# rosscomp_th.net
KiCad netlist of a schematic drawn in EAGLE
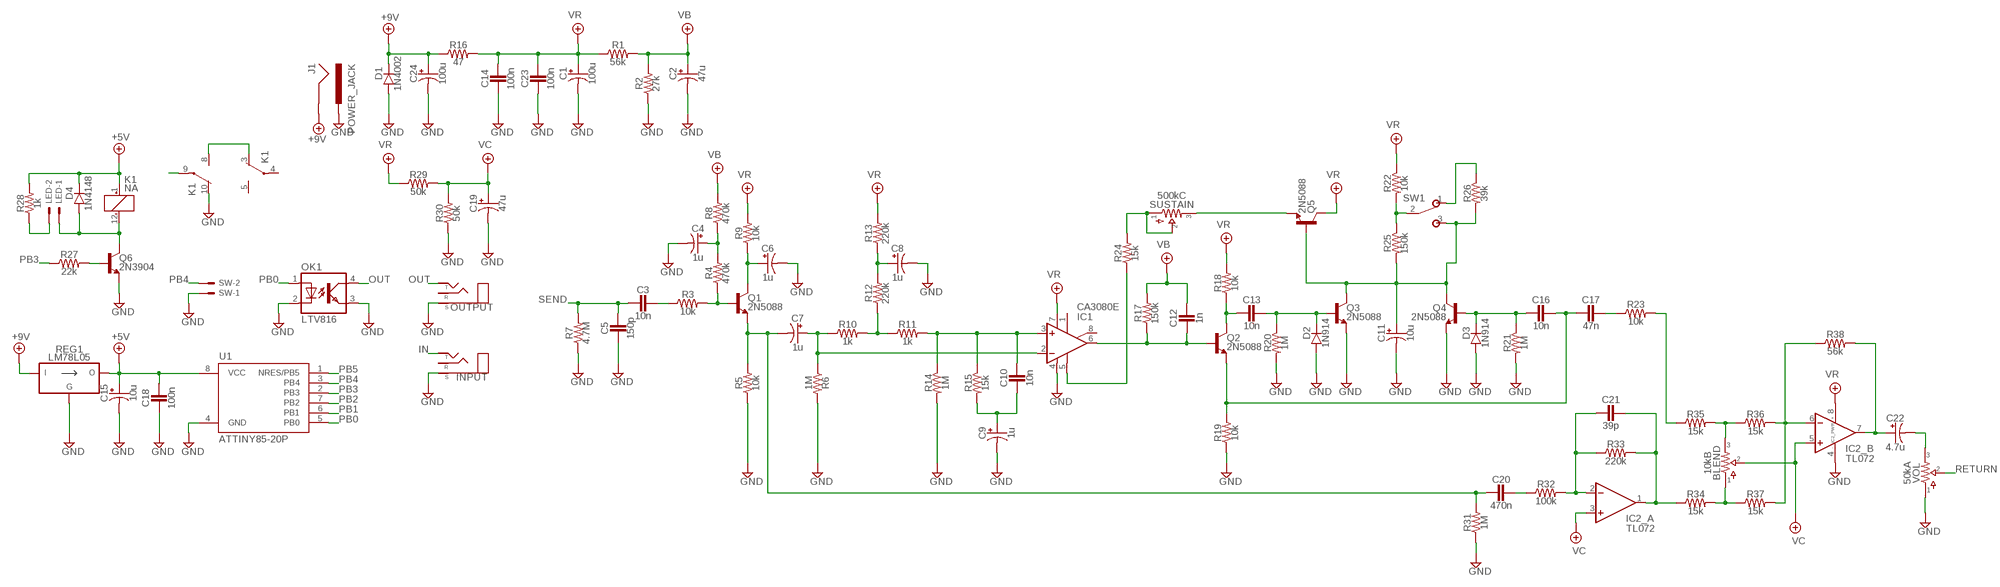
[diagram p0: schematic, sheet 1]

(export (version "E")
  (design (tool "Eeschema 10.0.6"))
  (components
    (comp (ref "BLEND")
      (value "10kB")
      (footprint "eagle-import:16MM")
      (libsource (lib "eagle-import") (part "POTS16MM"))
    )
    (comp (ref "C1")
      (value "100u")
      (footprint "eagle-import:050_020")
      (libsource (lib "eagle-import") (part "0500"))
    )
    (comp (ref "C2")
      (value "47u")
      (footprint "eagle-import:050_020")
      (libsource (lib "eagle-import") (part "0500"))
    )
    (comp (ref "C3")
      (value "10n")
      (footprint "eagle-import:BOX_SMALL")
      (libsource (lib "eagle-import") (part "CER/FILMBOX.1"))
    )
    (comp (ref "C4")
      (value "1u")
      (footprint "eagle-import:040_020")
      (libsource (lib "eagle-import") (part "0400"))
    )
    (comp (ref "C5")
      (value "150p")
      (footprint "eagle-import:050X030_025_2")
      (libsource (lib "eagle-import") (part "CER/FILM2"))
    )
    (comp (ref "C6")
      (value "1u")
      (footprint "eagle-import:040_020")
      (libsource (lib "eagle-import") (part "0400"))
    )
    (comp (ref "C7")
      (value "1u")
      (footprint "eagle-import:040_020")
      (libsource (lib "eagle-import") (part "0400"))
    )
    (comp (ref "C8")
      (value "1u")
      (footprint "eagle-import:040_020")
      (libsource (lib "eagle-import") (part "0400"))
    )
    (comp (ref "C9")
      (value "1u")
      (footprint "eagle-import:040_020")
      (libsource (lib "eagle-import") (part "0400"))
    )
    (comp (ref "C10")
      (value "10n")
      (footprint "eagle-import:BOX_SMALL")
      (libsource (lib "eagle-import") (part "CER/FILMBOX.1"))
    )
    (comp (ref "C11")
      (value "10u")
      (footprint "eagle-import:050_020")
      (libsource (lib "eagle-import") (part "0500"))
    )
    (comp (ref "C12")
      (value "1n")
      (footprint "eagle-import:BOX_SMALL")
      (libsource (lib "eagle-import") (part "CER/FILMBOX.1"))
    )
    (comp (ref "C13")
      (value "10n")
      (footprint "eagle-import:BOX_SMALL")
      (libsource (lib "eagle-import") (part "CER/FILMBOX.1"))
    )
    (comp (ref "C14")
      (value "100n")
      (footprint "eagle-import:050X030_025_2")
      (libsource (lib "eagle-import") (part "CER/FILM2"))
    )
    (comp (ref "C15")
      (value "10u")
      (footprint "eagle-import:050_020")
      (libsource (lib "eagle-import") (part "0500"))
    )
    (comp (ref "C16")
      (value "10n")
      (footprint "eagle-import:BOX_SMALL")
      (libsource (lib "eagle-import") (part "CER/FILMBOX.1"))
    )
    (comp (ref "C17")
      (value "47n")
      (footprint "eagle-import:BOX_SMALL")
      (libsource (lib "eagle-import") (part "CER/FILMBOX.1"))
    )
    (comp (ref "C18")
      (value "100n")
      (footprint "eagle-import:050X030_025_2")
      (libsource (lib "eagle-import") (part "CER/FILM2"))
    )
    (comp (ref "C19")
      (value "47u")
      (footprint "eagle-import:050_020")
      (libsource (lib "eagle-import") (part "0500"))
    )
    (comp (ref "C20")
      (value "470n")
      (footprint "eagle-import:BOX_MED")
      (libsource (lib "eagle-import") (part "CER/FILMBOX.2"))
    )
    (comp (ref "C21")
      (value "39p")
      (footprint "eagle-import:050X030_025_2")
      (libsource (lib "eagle-import") (part "CER/FILM2"))
    )
    (comp (ref "C22")
      (value "4.7u")
      (footprint "eagle-import:050_020")
      (libsource (lib "eagle-import") (part "0500"))
    )
    (comp (ref "C23")
      (value "100n")
      (footprint "eagle-import:050X030_025_2")
      (libsource (lib "eagle-import") (part "CER/FILM2"))
    )
    (comp (ref "C24")
      (value "100u")
      (footprint "eagle-import:050_020")
      (libsource (lib "eagle-import") (part "0500"))
    )
    (comp (ref "D1")
      (value "1N4002")
      (footprint "eagle-import:DO41-2")
      (libsource (lib "eagle-import") (part "DO41.2"))
    )
    (comp (ref "D2")
      (value "1N914")
      (footprint "eagle-import:DO35-2")
      (libsource (lib "eagle-import") (part "DO35.2"))
    )
    (comp (ref "D3")
      (value "1N914")
      (footprint "eagle-import:DO35-2")
      (libsource (lib "eagle-import") (part "DO35.2"))
    )
    (comp (ref "D4")
      (value "1N4148")
      (footprint "eagle-import:DO35-2")
      (libsource (lib "eagle-import") (part "DO35.2"))
    )
    (comp (ref "IC1")
      (value "CA3080E")
      (footprint "eagle-import:DIL0")
      (libsource (lib "eagle-import") (part "3080TH"))
    )
    (comp (ref "IC2")
      (value "TL072")
      (footprint "eagle-import:DIL0")
      (libsource (lib "eagle-import") (part "DUALTH"))
    )
    (comp (ref "INPUT")
      (value "STEREONMJ")
      (footprint "eagle-import:NMJ6HCD2")
      (libsource (lib "eagle-import") (part "STEREONMJ"))
    )
    (comp (ref "J1")
      (value "POWER_JACK")
      (footprint "eagle-import:POWER_JACK_PTH")
      (libsource (lib "eagle-import") (part "POWER_JACK"))
    )
    (comp (ref "K1") (value "NA") (footprint "eagle-import:NA") (libsource (lib "eagle-import") (part "NA")))
    (comp (ref "LED")
      (value "JST-XH-02-PIN-ROUND-PAD")
      (footprint "eagle-import:JST-XH-02-PACKAGE-ROUND-PAD")
      (libsource (lib "eagle-import") (part "JST-XH-02-PIN-ROUND-PAD"))
    )
    (comp (ref "OK1")
      (value "LTV816")
      (footprint "eagle-import:DIL04")
      (libsource (lib "eagle-import") (part "LTV816"))
    )
    (comp (ref "OUTPUT")
      (value "STEREONMJ")
      (footprint "eagle-import:NMJ6HCD2")
      (libsource (lib "eagle-import") (part "STEREONMJ"))
    )
    (comp (ref "Q1")
      (value "2N5088")
      (footprint "eagle-import:TO92-")
      (libsource (lib "eagle-import") (part "2N5088"))
    )
    (comp (ref "Q2")
      (value "2N5088")
      (footprint "eagle-import:TO92-")
      (libsource (lib "eagle-import") (part "2N5088"))
    )
    (comp (ref "Q3")
      (value "2N5088")
      (footprint "eagle-import:TO92-")
      (libsource (lib "eagle-import") (part "2N5088"))
    )
    (comp (ref "Q4")
      (value "2N5088")
      (footprint "eagle-import:TO92-")
      (libsource (lib "eagle-import") (part "2N5088"))
    )
    (comp (ref "Q5")
      (value "2N5088")
      (footprint "eagle-import:TO92-")
      (libsource (lib "eagle-import") (part "2N5088"))
    )
    (comp (ref "Q6")
      (value "2N3904")
      (footprint "eagle-import:TO92-")
      (libsource (lib "eagle-import") (part "2N3904"))
    )
    (comp (ref "R1")
      (value "56k")
      (footprint "eagle-import:R0207_3")
      (libsource (lib "eagle-import") (part "R_.3B"))
    )
    (comp (ref "R2")
      (value "27k")
      (footprint "eagle-import:R0207_3")
      (libsource (lib "eagle-import") (part "R_.3B"))
    )
    (comp (ref "R3")
      (value "10k")
      (footprint "eagle-import:R0207_3")
      (libsource (lib "eagle-import") (part "R_.3B"))
    )
    (comp (ref "R4")
      (value "470k")
      (footprint "eagle-import:R0207_3")
      (libsource (lib "eagle-import") (part "R_.3B"))
    )
    (comp (ref "R5")
      (value "10k")
      (footprint "eagle-import:R0207_3")
      (libsource (lib "eagle-import") (part "R_.3B"))
    )
    (comp (ref "R6")
      (value "1M")
      (footprint "eagle-import:R0207_3")
      (libsource (lib "eagle-import") (part "R_.3B"))
    )
    (comp (ref "R7")
      (value "4.7M")
      (footprint "eagle-import:R0207_3")
      (libsource (lib "eagle-import") (part "R_.3B"))
    )
    (comp (ref "R8")
      (value "470k")
      (footprint "eagle-import:R0207_3")
      (libsource (lib "eagle-import") (part "R_.3B"))
    )
    (comp (ref "R9")
      (value "10k")
      (footprint "eagle-import:R0207_3")
      (libsource (lib "eagle-import") (part "R_.3B"))
    )
    (comp (ref "R10")
      (value "1k")
      (footprint "eagle-import:R0207_3")
      (libsource (lib "eagle-import") (part "R_.3B"))
    )
    (comp (ref "R11")
      (value "1k")
      (footprint "eagle-import:R0207_3")
      (libsource (lib "eagle-import") (part "R_.3B"))
    )
    (comp (ref "R12")
      (value "220k")
      (footprint "eagle-import:R0207_3")
      (libsource (lib "eagle-import") (part "R_.3B"))
    )
    (comp (ref "R13")
      (value "220k")
      (footprint "eagle-import:R0207_3")
      (libsource (lib "eagle-import") (part "R_.3B"))
    )
    (comp (ref "R14")
      (value "1M")
      (footprint "eagle-import:R0207_3")
      (libsource (lib "eagle-import") (part "R_.3B"))
    )
    (comp (ref "R15")
      (value "15k")
      (footprint "eagle-import:R0207_3")
      (libsource (lib "eagle-import") (part "R_.3B"))
    )
    (comp (ref "R16")
      (value "47")
      (footprint "eagle-import:R0207_3")
      (libsource (lib "eagle-import") (part "R_.3B"))
    )
    (comp (ref "R17")
      (value "150k")
      (footprint "eagle-import:R0207_3")
      (libsource (lib "eagle-import") (part "R_.3B"))
    )
    (comp (ref "R18")
      (value "10k")
      (footprint "eagle-import:R0207_3")
      (libsource (lib "eagle-import") (part "R_.3B"))
    )
    (comp (ref "R19")
      (value "10k")
      (footprint "eagle-import:R0207_3")
      (libsource (lib "eagle-import") (part "R_.3B"))
    )
    (comp (ref "R20")
      (value "1M")
      (footprint "eagle-import:R0207_3")
      (libsource (lib "eagle-import") (part "R_.3B"))
    )
    (comp (ref "R21")
      (value "1M")
      (footprint "eagle-import:R0207_3")
      (libsource (lib "eagle-import") (part "R_.3B"))
    )
    (comp (ref "R22")
      (value "10k")
      (footprint "eagle-import:R0207_3")
      (libsource (lib "eagle-import") (part "R_.3B"))
    )
    (comp (ref "R23")
      (value "10k")
      (footprint "eagle-import:R0207_3")
      (libsource (lib "eagle-import") (part "R_.3B"))
    )
    (comp (ref "R24")
      (value "15k")
      (footprint "eagle-import:R0207_3")
      (libsource (lib "eagle-import") (part "R_.3B"))
    )
    (comp (ref "R25")
      (value "150k")
      (footprint "eagle-import:R0207_3")
      (libsource (lib "eagle-import") (part "R_.3B"))
    )
    (comp (ref "R26")
      (value "39k")
      (footprint "eagle-import:R0207_3")
      (libsource (lib "eagle-import") (part "R_.3B"))
    )
    (comp (ref "R27")
      (value "22k")
      (footprint "eagle-import:R0207_3")
      (libsource (lib "eagle-import") (part "R_.3B"))
    )
    (comp (ref "R28")
      (value "1k")
      (footprint "eagle-import:R0207_3")
      (libsource (lib "eagle-import") (part "R_.3B"))
    )
    (comp (ref "R29")
      (value "50k")
      (footprint "eagle-import:R0207_3")
      (libsource (lib "eagle-import") (part "R_.3B"))
    )
    (comp (ref "R30")
      (value "50k")
      (footprint "eagle-import:R0207_3")
      (libsource (lib "eagle-import") (part "R_.3B"))
    )
    (comp (ref "R31")
      (value "1M")
      (footprint "eagle-import:R0207_3")
      (libsource (lib "eagle-import") (part "R_.3B"))
    )
    (comp (ref "R32")
      (value "100k")
      (footprint "eagle-import:R0207_3")
      (libsource (lib "eagle-import") (part "R_.3B"))
    )
    (comp (ref "R33")
      (value "220k")
      (footprint "eagle-import:R0207_3")
      (libsource (lib "eagle-import") (part "R_.3B"))
    )
    (comp (ref "R34")
      (value "15k")
      (footprint "eagle-import:R0207_3")
      (libsource (lib "eagle-import") (part "R_.3B"))
    )
    (comp (ref "R35")
      (value "15k")
      (footprint "eagle-import:R0207_3")
      (libsource (lib "eagle-import") (part "R_.3B"))
    )
    (comp (ref "R36")
      (value "15k")
      (footprint "eagle-import:R0207_3")
      (libsource (lib "eagle-import") (part "R_.3B"))
    )
    (comp (ref "R37")
      (value "15k")
      (footprint "eagle-import:R0207_3")
      (libsource (lib "eagle-import") (part "R_.3B"))
    )
    (comp (ref "R38")
      (value "56k")
      (footprint "eagle-import:R0207_3")
      (libsource (lib "eagle-import") (part "R_.3B"))
    )
    (comp (ref "REG1")
      (value "LM78L05")
      (footprint "eagle-import:TO92-")
      (libsource (lib "eagle-import") (part "LM78L05"))
    )
    (comp (ref "SUSTAIN")
      (value "500kC")
      (footprint "eagle-import:16MM")
      (libsource (lib "eagle-import") (part "POTS16MM"))
    )
    (comp (ref "SW")
      (value "JST-XH-02-PIN-ROUND-PAD")
      (footprint "eagle-import:JST-XH-02-PACKAGE-ROUND-PAD")
      (libsource (lib "eagle-import") (part "JST-XH-02-PIN-ROUND-PAD"))
    )
    (comp (ref "SW1")
      (value "SPDT")
      (footprint "eagle-import:M9040P")
      (libsource (lib "eagle-import") (part "SPDT"))
    )
    (comp (ref "U1")
      (value "ATTINY85-20P")
      (footprint "eagle-import:PDIP08_300MIL")
      (libsource (lib "eagle-import") (part "ATTINY85P-20"))
    )
    (comp (ref "VOL")
      (value "50kA")
      (footprint "eagle-import:16MM")
      (libsource (lib "eagle-import") (part "POTS16MM"))
    )
  )
  (nets
    (net (code "1") (name "+5V") (class "Default")
      (node (ref "C15") (pin "+") (pinfunction "+_+") (pintype "passive"))
      (node (ref "C18") (pin "1") (pinfunction "1_1") (pintype "passive"))
      (node (ref "D4") (pin "C") (pinfunction "C_C") (pintype "passive"))
      (node (ref "K1") (pin "1") (pinfunction "+_1") (pintype "passive"))
      (node (ref "R28") (pin "2") (pinfunction "2_2") (pintype "passive"))
      (node (ref "REG1") (pin "3") (pinfunction "VO_3") (pintype "passive"))
      (node (ref "U1") (pin "8") (pinfunction "VCC_8") (pintype "power_in"))
    )
    (net (code "2") (name "+9V") (class "Default")
      (node (ref "C24") (pin "+") (pinfunction "+_+") (pintype "passive"))
      (node (ref "D1") (pin "C") (pinfunction "C_C") (pintype "passive"))
      (node (ref "J1") (pin "GND") (pinfunction "GND_GND") (pintype "bidirectional"))
      (node (ref "R16") (pin "1") (pinfunction "1_1") (pintype "passive"))
      (node (ref "REG1") (pin "1") (pinfunction "VI_1") (pintype "input"))
    )
    (net (code "3") (name "/IN") (class "Default")
      (node (ref "INPUT") (pin "T") (pinfunction "T_T") (pintype "passive"))
    )
    (net (code "4") (name "/OUT") (class "Default")
      (node (ref "OK1") (pin "4") (pinfunction "COL_4") (pintype "passive"))
      (node (ref "OUTPUT") (pin "T") (pinfunction "T_T") (pintype "passive"))
    )
    (net (code "5") (name "/PB0") (class "Default")
      (node (ref "OK1") (pin "1") (pinfunction "A_1") (pintype "passive"))
      (node (ref "U1") (pin "5") (pinfunction "PB0_5") (pintype "bidirectional"))
    )
    (net (code "6") (name "/PB1") (class "Default")
      (node (ref "U1") (pin "6") (pinfunction "PB1_6") (pintype "bidirectional"))
    )
    (net (code "7") (name "/PB2") (class "Default")
      (node (ref "U1") (pin "7") (pinfunction "PB2_7") (pintype "bidirectional"))
    )
    (net (code "8") (name "/PB3") (class "Default")
      (node (ref "R27") (pin "1") (pinfunction "1_1") (pintype "passive"))
      (node (ref "U1") (pin "2") (pinfunction "PB3_2") (pintype "bidirectional"))
    )
    (net (code "9") (name "/PB4") (class "Default")
      (node (ref "SW") (pin "2") (pinfunction "S_2") (pintype "passive"))
      (node (ref "U1") (pin "3") (pinfunction "PB4_3") (pintype "bidirectional"))
    )
    (net (code "10") (name "/PB5") (class "Default")
      (node (ref "U1") (pin "1") (pinfunction "NRES/PB5_1") (pintype "bidirectional"))
    )
    (net (code "11") (name "/RETURN") (class "Default")
      (node (ref "VOL") (pin "2") (pinfunction "2_2") (pintype "passive"))
    )
    (net (code "12") (name "/SEND") (class "Default")
      (node (ref "C3") (pin "2") (pinfunction "2_2") (pintype "passive"))
      (node (ref "C5") (pin "1") (pinfunction "1_1") (pintype "passive"))
      (node (ref "R7") (pin "2") (pinfunction "2_2") (pintype "passive"))
    )
    (net (code "13") (name "GND") (class "Default")
      (node (ref "C1") (pin "-") (pinfunction "-_-") (pintype "passive"))
      (node (ref "C11") (pin "-") (pinfunction "-_-") (pintype "passive"))
      (node (ref "C14") (pin "1") (pinfunction "1_1") (pintype "passive"))
      (node (ref "C15") (pin "-") (pinfunction "-_-") (pintype "passive"))
      (node (ref "C18") (pin "2") (pinfunction "2_2") (pintype "passive"))
      (node (ref "C19") (pin "-") (pinfunction "-_-") (pintype "passive"))
      (node (ref "C2") (pin "-") (pinfunction "-_-") (pintype "passive"))
      (node (ref "C23") (pin "1") (pinfunction "1_1") (pintype "passive"))
      (node (ref "C24") (pin "-") (pinfunction "-_-") (pintype "passive"))
      (node (ref "C4") (pin "-") (pinfunction "-_-") (pintype "passive"))
      (node (ref "C5") (pin "2") (pinfunction "2_2") (pintype "passive"))
      (node (ref "C6") (pin "-") (pinfunction "-_-") (pintype "passive"))
      (node (ref "C8") (pin "-") (pinfunction "-_-") (pintype "passive"))
      (node (ref "C9") (pin "-") (pinfunction "-_-") (pintype "passive"))
      (node (ref "D1") (pin "A") (pinfunction "A_A") (pintype "passive"))
      (node (ref "D2") (pin "A") (pinfunction "A_A") (pintype "passive"))
      (node (ref "D3") (pin "A") (pinfunction "A_A") (pintype "passive"))
      (node (ref "IC1") (pin "4") (pinfunction "V-_4") (pintype "power_in"))
      (node (ref "IC2") (pin "4") (pinfunction "V-_4") (pintype "power_in"))
      (node (ref "INPUT") (pin "S") (pinfunction "S_S") (pintype "passive"))
      (node (ref "J1") (pin "PWR") (pinfunction "PWR_PWR") (pintype "bidirectional"))
      (node (ref "K1") (pin "10") (pinfunction "O_10") (pintype "passive"))
      (node (ref "OK1") (pin "2") (pinfunction "C_2") (pintype "passive"))
      (node (ref "OK1") (pin "3") (pinfunction "EMIT_3") (pintype "passive"))
      (node (ref "OUTPUT") (pin "S") (pinfunction "S_S") (pintype "passive"))
      (node (ref "Q3") (pin "3") (pinfunction "E_3") (pintype "passive"))
      (node (ref "Q4") (pin "3") (pinfunction "E_3") (pintype "passive"))
      (node (ref "Q6") (pin "3") (pinfunction "E_3") (pintype "passive"))
      (node (ref "R14") (pin "2") (pinfunction "2_2") (pintype "passive"))
      (node (ref "R19") (pin "1") (pinfunction "1_1") (pintype "passive"))
      (node (ref "R2") (pin "1") (pinfunction "1_1") (pintype "passive"))
      (node (ref "R20") (pin "2") (pinfunction "2_2") (pintype "passive"))
      (node (ref "R21") (pin "2") (pinfunction "2_2") (pintype "passive"))
      (node (ref "R30") (pin "1") (pinfunction "1_1") (pintype "passive"))
      (node (ref "R31") (pin "1") (pinfunction "1_1") (pintype "passive"))
      (node (ref "R5") (pin "1") (pinfunction "1_1") (pintype "passive"))
      (node (ref "R6") (pin "2") (pinfunction "2_2") (pintype "passive"))
      (node (ref "R7") (pin "1") (pinfunction "1_1") (pintype "passive"))
      (node (ref "REG1") (pin "2") (pinfunction "GND_2") (pintype "passive"))
      (node (ref "SW") (pin "1") (pinfunction "S_1") (pintype "passive"))
      (node (ref "U1") (pin "4") (pinfunction "GND_4") (pintype "power_in"))
      (node (ref "VOL") (pin "1") (pinfunction "1_1") (pintype "passive"))
    )
    (net (code "14") (name "Net-(BLEND-Pad1)") (class "Default")
      (node (ref "BLEND") (pin "1") (pinfunction "1_1") (pintype "passive"))
      (node (ref "R34") (pin "2") (pinfunction "2_2") (pintype "passive"))
      (node (ref "R37") (pin "1") (pinfunction "1_1") (pintype "passive"))
    )
    (net (code "15") (name "Net-(BLEND-Pad3)") (class "Default")
      (node (ref "BLEND") (pin "3") (pinfunction "3_3") (pintype "passive"))
      (node (ref "R35") (pin "2") (pinfunction "2_2") (pintype "passive"))
      (node (ref "R36") (pin "1") (pinfunction "1_1") (pintype "passive"))
    )
    (net (code "16") (name "Net-(C3-Pad1)") (class "Default")
      (node (ref "C3") (pin "1") (pinfunction "1_1") (pintype "passive"))
      (node (ref "R3") (pin "1") (pinfunction "1_1") (pintype "passive"))
    )
    (net (code "17") (name "Net-(C4-Pad+)") (class "Default")
      (node (ref "C4") (pin "+") (pinfunction "+_+") (pintype "passive"))
      (node (ref "R4") (pin "2") (pinfunction "2_2") (pintype "passive"))
      (node (ref "R8") (pin "1") (pinfunction "1_1") (pintype "passive"))
    )
    (net (code "18") (name "Net-(C8-Pad+)") (class "Default")
      (node (ref "C8") (pin "+") (pinfunction "+_+") (pintype "passive"))
      (node (ref "R12") (pin "2") (pinfunction "2_2") (pintype "passive"))
      (node (ref "R13") (pin "1") (pinfunction "1_1") (pintype "passive"))
    )
    (net (code "19") (name "Net-(C10-Pad2)") (class "Default")
      (node (ref "C10") (pin "2") (pinfunction "2_2") (pintype "passive"))
      (node (ref "C9") (pin "+") (pinfunction "+_+") (pintype "passive"))
      (node (ref "R15") (pin "2") (pinfunction "2_2") (pintype "passive"))
    )
    (net (code "20") (name "Net-(C17-Pad1)") (class "Default")
      (node (ref "C17") (pin "1") (pinfunction "1_1") (pintype "passive"))
      (node (ref "R23") (pin "1") (pinfunction "1_1") (pintype "passive"))
    )
    (net (code "21") (name "Net-(C20-Pad1)") (class "Default")
      (node (ref "C20") (pin "1") (pinfunction "1_1") (pintype "passive"))
      (node (ref "R32") (pin "1") (pinfunction "1_1") (pintype "passive"))
    )
    (net (code "22") (name "Net-(C22-Pad-)") (class "Default")
      (node (ref "C22") (pin "-") (pinfunction "-_-") (pintype "passive"))
      (node (ref "VOL") (pin "3") (pinfunction "3_3") (pintype "passive"))
    )
    (net (code "23") (name "Net-(IC1-+IN)") (class "Default")
      (node (ref "C10") (pin "1") (pinfunction "1_1") (pintype "passive"))
      (node (ref "IC1") (pin "3") (pinfunction "+IN_3") (pintype "input"))
      (node (ref "R11") (pin "2") (pinfunction "2_2") (pintype "passive"))
      (node (ref "R14") (pin "1") (pinfunction "1_1") (pintype "passive"))
      (node (ref "R15") (pin "1") (pinfunction "1_1") (pintype "passive"))
    )
    (net (code "24") (name "Net-(IC1--IN)") (class "Default")
      (node (ref "C7") (pin "+") (pinfunction "+_+") (pintype "passive"))
      (node (ref "IC1") (pin "2") (pinfunction "-IN_2") (pintype "input"))
      (node (ref "R10") (pin "1") (pinfunction "1_1") (pintype "passive"))
      (node (ref "R6") (pin "1") (pinfunction "1_1") (pintype "passive"))
    )
    (net (code "25") (name "Net-(IC1-OPT)") (class "Default")
      (node (ref "IC1") (pin "5") (pinfunction "OPT_5") (pintype "passive"))
      (node (ref "R24") (pin "1") (pinfunction "1_1") (pintype "passive"))
    )
    (net (code "26") (name "Net-(IC1-OUT)") (class "Default")
      (node (ref "C12") (pin "2") (pinfunction "2_2") (pintype "passive"))
      (node (ref "IC1") (pin "6") (pinfunction "OUT_6") (pintype "output"))
      (node (ref "Q2") (pin "2") (pinfunction "B_2") (pintype "passive"))
      (node (ref "R17") (pin "1") (pinfunction "1_1") (pintype "passive"))
    )
    (net (code "27") (name "Net-(IC2A--IN)") (class "Default")
      (node (ref "C21") (pin "2") (pinfunction "2_2") (pintype "passive"))
      (node (ref "IC2") (pin "2") (pinfunction "-IN_2") (pintype "input"))
      (node (ref "R32") (pin "2") (pinfunction "2_2") (pintype "passive"))
      (node (ref "R33") (pin "1") (pinfunction "1_1") (pintype "passive"))
    )
    (net (code "28") (name "Net-(IC2A-OUT)") (class "Default")
      (node (ref "C21") (pin "1") (pinfunction "1_1") (pintype "passive"))
      (node (ref "IC2") (pin "1") (pinfunction "OUT_1") (pintype "output"))
      (node (ref "R33") (pin "2") (pinfunction "2_2") (pintype "passive"))
      (node (ref "R34") (pin "1") (pinfunction "1_1") (pintype "passive"))
    )
    (net (code "29") (name "Net-(IC2B--IN)") (class "Default")
      (node (ref "IC2") (pin "6") (pinfunction "-IN_6") (pintype "input"))
      (node (ref "R36") (pin "2") (pinfunction "2_2") (pintype "passive"))
      (node (ref "R37") (pin "2") (pinfunction "2_2") (pintype "passive"))
      (node (ref "R38") (pin "1") (pinfunction "1_1") (pintype "passive"))
    )
    (net (code "30") (name "Net-(IC2B-OUT)") (class "Default")
      (node (ref "C22") (pin "+") (pinfunction "+_+") (pintype "passive"))
      (node (ref "IC2") (pin "7") (pinfunction "OUT_7") (pintype "output"))
      (node (ref "R38") (pin "2") (pinfunction "2_2") (pintype "passive"))
    )
    (net (code "31") (name "Net-(K1A--)") (class "Default")
      (node (ref "D4") (pin "A") (pinfunction "A_A") (pintype "passive"))
      (node (ref "K1") (pin "12") (pinfunction "-_12") (pintype "passive"))
      (node (ref "LED") (pin "1") (pinfunction "S_1") (pintype "passive"))
      (node (ref "Q6") (pin "1") (pinfunction "C_1") (pintype "passive"))
    )
    (net (code "32") (name "Net-(K1B-O)") (class "Default")
      (node (ref "K1") (pin "3") (pinfunction "O_3") (pintype "passive"))
      (node (ref "K1") (pin "8") (pinfunction "S_8") (pintype "passive"))
    )
    (net (code "33") (name "Net-(LEDB-S)") (class "Default")
      (node (ref "LED") (pin "2") (pinfunction "S_2") (pintype "passive"))
      (node (ref "R28") (pin "1") (pinfunction "1_1") (pintype "passive"))
    )
    (net (code "34") (name "Net-(Q1-B)") (class "Default")
      (node (ref "Q1") (pin "2") (pinfunction "B_2") (pintype "passive"))
      (node (ref "R3") (pin "2") (pinfunction "2_2") (pintype "passive"))
      (node (ref "R4") (pin "1") (pinfunction "1_1") (pintype "passive"))
    )
    (net (code "35") (name "Net-(Q1-C)") (class "Default")
      (node (ref "C6") (pin "+") (pinfunction "+_+") (pintype "passive"))
      (node (ref "Q1") (pin "1") (pinfunction "C_1") (pintype "passive"))
      (node (ref "R9") (pin "1") (pinfunction "1_1") (pintype "passive"))
    )
    (net (code "36") (name "Net-(Q1-E)") (class "Default")
      (node (ref "C20") (pin "2") (pinfunction "2_2") (pintype "passive"))
      (node (ref "C7") (pin "-") (pinfunction "-_-") (pintype "passive"))
      (node (ref "Q1") (pin "3") (pinfunction "E_3") (pintype "passive"))
      (node (ref "R31") (pin "2") (pinfunction "2_2") (pintype "passive"))
      (node (ref "R5") (pin "2") (pinfunction "2_2") (pintype "passive"))
    )
    (net (code "37") (name "Net-(Q2-C)") (class "Default")
      (node (ref "C13") (pin "2") (pinfunction "2_2") (pintype "passive"))
      (node (ref "Q2") (pin "1") (pinfunction "C_1") (pintype "passive"))
      (node (ref "R18") (pin "1") (pinfunction "1_1") (pintype "passive"))
    )
    (net (code "38") (name "Net-(Q2-E)") (class "Default")
      (node (ref "C16") (pin "1") (pinfunction "1_1") (pintype "passive"))
      (node (ref "C17") (pin "2") (pinfunction "2_2") (pintype "passive"))
      (node (ref "Q2") (pin "3") (pinfunction "E_3") (pintype "passive"))
      (node (ref "R19") (pin "2") (pinfunction "2_2") (pintype "passive"))
    )
    (net (code "39") (name "Net-(Q3-B)") (class "Default")
      (node (ref "C13") (pin "1") (pinfunction "1_1") (pintype "passive"))
      (node (ref "D2") (pin "C") (pinfunction "C_C") (pintype "passive"))
      (node (ref "Q3") (pin "2") (pinfunction "B_2") (pintype "passive"))
      (node (ref "R20") (pin "1") (pinfunction "1_1") (pintype "passive"))
    )
    (net (code "40") (name "Net-(Q3-C)") (class "Default")
      (node (ref "C11") (pin "+") (pinfunction "+_+") (pintype "passive"))
      (node (ref "Q3") (pin "1") (pinfunction "C_1") (pintype "passive"))
      (node (ref "Q4") (pin "1") (pinfunction "C_1") (pintype "passive"))
      (node (ref "Q5") (pin "2") (pinfunction "B_2") (pintype "passive"))
      (node (ref "R25") (pin "2") (pinfunction "2_2") (pintype "passive"))
      (node (ref "R26") (pin "2") (pinfunction "2_2") (pintype "passive"))
      (node (ref "SW1") (pin "3") (pinfunction "S_3") (pintype "passive"))
    )
    (net (code "41") (name "Net-(Q4-B)") (class "Default")
      (node (ref "C16") (pin "2") (pinfunction "2_2") (pintype "passive"))
      (node (ref "D3") (pin "C") (pinfunction "C_C") (pintype "passive"))
      (node (ref "Q4") (pin "2") (pinfunction "B_2") (pintype "passive"))
      (node (ref "R21") (pin "1") (pinfunction "1_1") (pintype "passive"))
    )
    (net (code "42") (name "Net-(Q5-E)") (class "Default")
      (node (ref "Q5") (pin "3") (pinfunction "E_3") (pintype "passive"))
      (node (ref "SUSTAIN") (pin "3") (pinfunction "3_3") (pintype "passive"))
    )
    (net (code "43") (name "Net-(Q6-B)") (class "Default")
      (node (ref "Q6") (pin "2") (pinfunction "B_2") (pintype "passive"))
      (node (ref "R27") (pin "2") (pinfunction "2_2") (pintype "passive"))
    )
    (net (code "44") (name "Net-(R10-Pad2)") (class "Default")
      (node (ref "R10") (pin "2") (pinfunction "2_2") (pintype "passive"))
      (node (ref "R11") (pin "1") (pinfunction "1_1") (pintype "passive"))
      (node (ref "R12") (pin "1") (pinfunction "1_1") (pintype "passive"))
    )
    (net (code "45") (name "Net-(R23-Pad2)") (class "Default")
      (node (ref "R23") (pin "2") (pinfunction "2_2") (pintype "passive"))
      (node (ref "R35") (pin "1") (pinfunction "1_1") (pintype "passive"))
    )
    (net (code "46") (name "Net-(R24-Pad2)") (class "Default")
      (node (ref "R24") (pin "2") (pinfunction "2_2") (pintype "passive"))
      (node (ref "SUSTAIN") (pin "1") (pinfunction "1_1") (pintype "passive"))
      (node (ref "SUSTAIN") (pin "2") (pinfunction "2_2") (pintype "passive"))
    )
    (net (code "47") (name "Net-(SW1-O)") (class "Default")
      (node (ref "R26") (pin "1") (pinfunction "1_1") (pintype "passive"))
      (node (ref "SW1") (pin "1") (pinfunction "O_1") (pintype "passive"))
    )
    (net (code "48") (name "Net-(SW1-P)") (class "Default")
      (node (ref "R22") (pin "2") (pinfunction "2_2") (pintype "passive"))
      (node (ref "R25") (pin "1") (pinfunction "1_1") (pintype "passive"))
      (node (ref "SW1") (pin "2") (pinfunction "P_2") (pintype "passive"))
    )
    (net (code "49") (name "VB") (class "Default")
      (node (ref "C12") (pin "1") (pinfunction "1_1") (pintype "passive"))
      (node (ref "C2") (pin "+") (pinfunction "+_+") (pintype "passive"))
      (node (ref "R1") (pin "2") (pinfunction "2_2") (pintype "passive"))
      (node (ref "R17") (pin "2") (pinfunction "2_2") (pintype "passive"))
      (node (ref "R2") (pin "2") (pinfunction "2_2") (pintype "passive"))
      (node (ref "R8") (pin "2") (pinfunction "2_2") (pintype "passive"))
    )
    (net (code "50") (name "VC") (class "Default")
      (node (ref "BLEND") (pin "2") (pinfunction "2_2") (pintype "passive"))
      (node (ref "C19") (pin "+") (pinfunction "+_+") (pintype "passive"))
      (node (ref "IC2") (pin "3") (pinfunction "+IN_3") (pintype "input"))
      (node (ref "IC2") (pin "5") (pinfunction "+IN_5") (pintype "input"))
      (node (ref "R29") (pin "2") (pinfunction "2_2") (pintype "passive"))
      (node (ref "R30") (pin "2") (pinfunction "2_2") (pintype "passive"))
    )
    (net (code "51") (name "VR") (class "Default")
      (node (ref "C1") (pin "+") (pinfunction "+_+") (pintype "passive"))
      (node (ref "C14") (pin "2") (pinfunction "2_2") (pintype "passive"))
      (node (ref "C23") (pin "2") (pinfunction "2_2") (pintype "passive"))
      (node (ref "IC1") (pin "7") (pinfunction "V+_7") (pintype "power_in"))
      (node (ref "IC2") (pin "8") (pinfunction "V+_8") (pintype "power_in"))
      (node (ref "Q5") (pin "1") (pinfunction "C_1") (pintype "passive"))
      (node (ref "R1") (pin "1") (pinfunction "1_1") (pintype "passive"))
      (node (ref "R13") (pin "2") (pinfunction "2_2") (pintype "passive"))
      (node (ref "R16") (pin "2") (pinfunction "2_2") (pintype "passive"))
      (node (ref "R18") (pin "2") (pinfunction "2_2") (pintype "passive"))
      (node (ref "R22") (pin "1") (pinfunction "1_1") (pintype "passive"))
      (node (ref "R29") (pin "1") (pinfunction "1_1") (pintype "passive"))
      (node (ref "R9") (pin "2") (pinfunction "2_2") (pintype "passive"))
    )
    (net (code "52") (name "unconnected-(IC1-ON1-Pad1)") (class "Default")
      (node (ref "IC1") (pin "1") (pinfunction "ON1_1") (pintype "passive"))
    )
    (net (code "53") (name "unconnected-(IC1-ON2-Pad8)") (class "Default")
      (node (ref "IC1") (pin "8") (pinfunction "ON2_8") (pintype "passive"))
    )
    (net (code "54") (name "unconnected-(INPUT-PadR)") (class "Default")
      (node (ref "INPUT") (pin "R") (pinfunction "R_R") (pintype "passive"))
    )
    (net (code "55") (name "unconnected-(K1B-P-Pad4)") (class "Default")
      (node (ref "K1") (pin "4") (pinfunction "P_4") (pintype "passive"))
    )
    (net (code "56") (name "unconnected-(K1B-S-Pad5)") (class "Default")
      (node (ref "K1") (pin "5") (pinfunction "S_5") (pintype "passive"))
    )
    (net (code "57") (name "unconnected-(K1C-P-Pad9)") (class "Default")
      (node (ref "K1") (pin "9") (pinfunction "P_9") (pintype "passive"))
    )
    (net (code "58") (name "unconnected-(OUTPUT-PadR)") (class "Default")
      (node (ref "OUTPUT") (pin "R") (pinfunction "R_R") (pintype "passive"))
    )
  )
)
